# LPCB227_-_ACCELS.net
KiCad netlist of a schematic drawn in Altium Designer
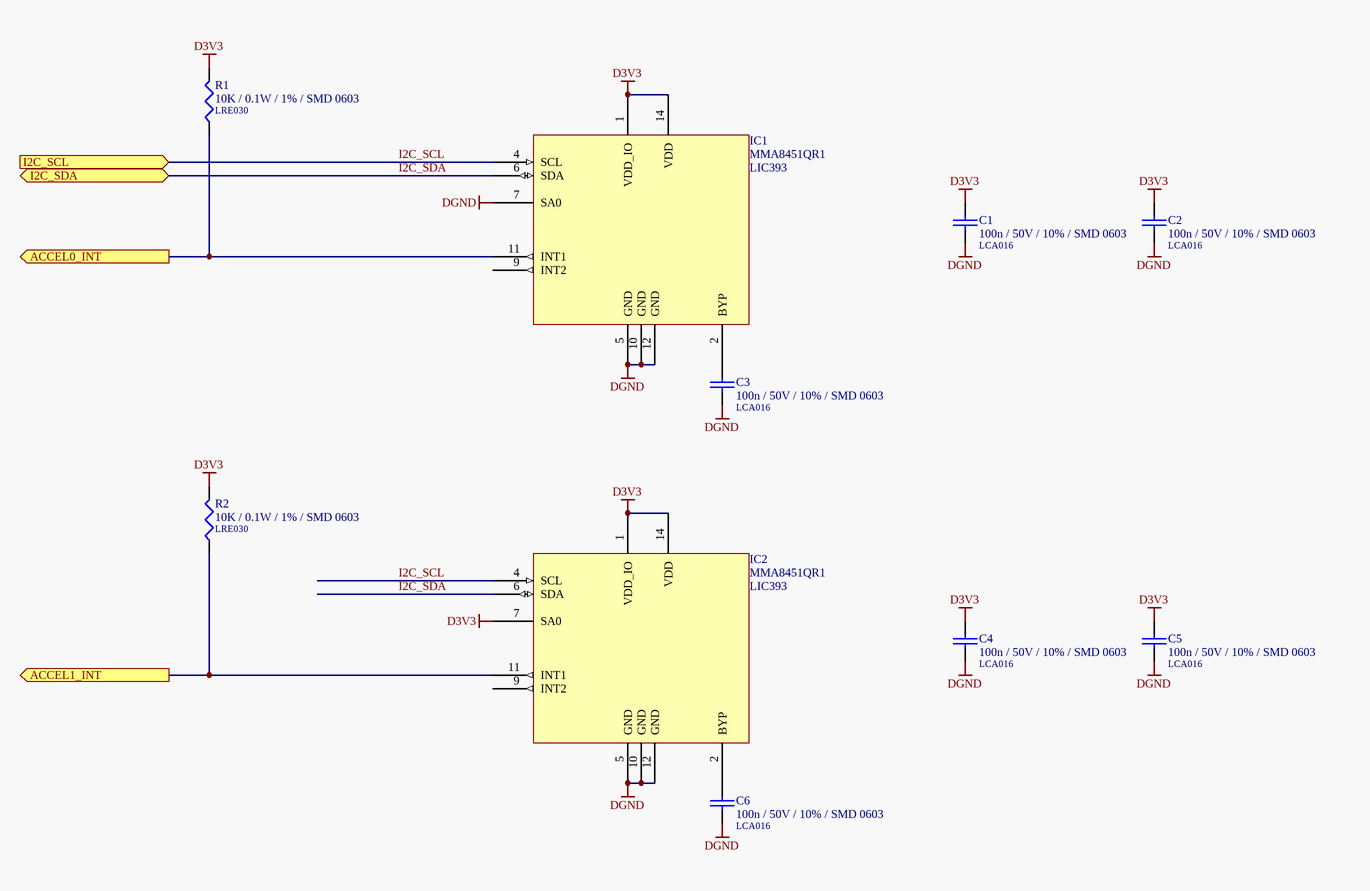
[diagram p0: LPCB227 - ACCELS.SchDoc]

(export (version "E")
  (design (tool "Eeschema 10.0.6"))
  (components
    (comp (ref "C1")
      (value "100n / 50V / 10% / SMD 0603")
      (footprint "LFP011__CC1608-0603-IPC7351_B")
      (description "Capacitor, Ceramic Chip, 100nF (0.1uF), 50V, 5%, SMD 0603 [LCA016]")
      (fields (field (name "LDL_NUMBER") "LCA016"))
      (libsource (lib "LDL_Capacitors") (part "100n / 50V / 10% / SMD 0603"))
    )
    (comp (ref "C2")
      (value "100n / 50V / 10% / SMD 0603")
      (footprint "LFP011__CC1608-0603-IPC7351_B")
      (description "Capacitor, Ceramic Chip, 100nF (0.1uF), 50V, 5%, SMD 0603 [LCA016]")
      (fields (field (name "LDL_NUMBER") "LCA016"))
      (libsource (lib "LDL_Capacitors") (part "100n / 50V / 10% / SMD 0603"))
    )
    (comp (ref "C3")
      (value "100n / 50V / 10% / SMD 0603")
      (footprint "LFP011__CC1608-0603-IPC7351_B")
      (description "Capacitor, Ceramic Chip, 100nF (0.1uF), 50V, 5%, SMD 0603 [LCA016]")
      (fields (field (name "LDL_NUMBER") "LCA016"))
      (libsource (lib "LDL_Capacitors") (part "100n / 50V / 10% / SMD 0603"))
    )
    (comp (ref "C4")
      (value "100n / 50V / 10% / SMD 0603")
      (footprint "LFP011__CC1608-0603-IPC7351_B")
      (description "Capacitor, Ceramic Chip, 100nF (0.1uF), 50V, 5%, SMD 0603 [LCA016]")
      (fields (field (name "LDL_NUMBER") "LCA016"))
      (libsource (lib "LDL_Capacitors") (part "100n / 50V / 10% / SMD 0603"))
    )
    (comp (ref "C5")
      (value "100n / 50V / 10% / SMD 0603")
      (footprint "LFP011__CC1608-0603-IPC7351_B")
      (description "Capacitor, Ceramic Chip, 100nF (0.1uF), 50V, 5%, SMD 0603 [LCA016]")
      (fields (field (name "LDL_NUMBER") "LCA016"))
      (libsource (lib "LDL_Capacitors") (part "100n / 50V / 10% / SMD 0603"))
    )
    (comp (ref "C6")
      (value "100n / 50V / 10% / SMD 0603")
      (footprint "LFP011__CC1608-0603-IPC7351_B")
      (description "Capacitor, Ceramic Chip, 100nF (0.1uF), 50V, 5%, SMD 0603 [LCA016]")
      (fields (field (name "LDL_NUMBER") "LCA016"))
      (libsource (lib "LDL_Capacitors") (part "100n / 50V / 10% / SMD 0603"))
    )
    (comp (ref "IC1")
      (value "MMA8451QR1")
      (footprint "LFP051__QFN16")
      (description "IC, Accelerometer, 3-Axis, 3.3V, I2C, SMD QFN16 [LIC393]")
      (fields (field (name "LDL_NUMBER") "LIC393"))
      (libsource (lib "LDL_Semiconductors") (part "MMA8451QR1"))
    )
    (comp (ref "IC2")
      (value "MMA8451QR1")
      (footprint "LFP051__QFN16")
      (description "IC, Accelerometer, 3-Axis, 3.3V, I2C, SMD QFN16 [LIC393]")
      (fields (field (name "LDL_NUMBER") "LIC393"))
      (libsource (lib "LDL_Semiconductors") (part "MMA8451QR1"))
    )
    (comp (ref "R1")
      (value "10K / 0.1W / 1% / SMD 0603")
      (footprint "LFP020__CR1608-0603-IPC7351_B")
      (description "Resistor, Ceramic Chip, 10K, 0.1W, 1%, SMD 0603 [LRE030]")
      (fields (field (name "LDL_NUMBER") "LRE030"))
      (libsource (lib "LDL_Resistors") (part "10K / 0.1W / 1% / SMD 0603"))
    )
    (comp (ref "R2")
      (value "10K / 0.1W / 1% / SMD 0603")
      (footprint "LFP020__CR1608-0603-IPC7351_B")
      (description "Resistor, Ceramic Chip, 10K, 0.1W, 1%, SMD 0603 [LRE030]")
      (fields (field (name "LDL_NUMBER") "LRE030"))
      (libsource (lib "LDL_Resistors") (part "10K / 0.1W / 1% / SMD 0603"))
    )
  )
  (nets
    (net (code "1") (name "/ACCEL0_INT") (class "Default")
      (node (ref "IC1") (pin "11") (pinfunction "INT1_11") (pintype "output"))
      (node (ref "R1") (pin "1") (pintype "passive"))
    )
    (net (code "2") (name "/ACCEL1_INT") (class "Default")
      (node (ref "IC2") (pin "11") (pinfunction "INT1_11") (pintype "output"))
      (node (ref "R2") (pin "1") (pintype "passive"))
    )
    (net (code "3") (name "/I2C_SCL") (class "Default")
      (node (ref "IC1") (pin "4") (pinfunction "SCL_4") (pintype "input"))
      (node (ref "IC2") (pin "4") (pinfunction "SCL_4") (pintype "input"))
    )
    (net (code "4") (name "/I2C_SDA") (class "Default")
      (node (ref "IC1") (pin "6") (pinfunction "SDA_6") (pintype "bidirectional"))
      (node (ref "IC2") (pin "6") (pinfunction "SDA_6") (pintype "bidirectional"))
    )
    (net (code "5") (name "D3V3") (class "Default")
      (node (ref "C1") (pin "1") (pintype "passive"))
      (node (ref "C2") (pin "1") (pintype "passive"))
      (node (ref "C4") (pin "1") (pintype "passive"))
      (node (ref "C5") (pin "1") (pintype "passive"))
      (node (ref "IC1") (pin "1") (pinfunction "VDD_IO_1") (pintype "power_in"))
      (node (ref "IC1") (pin "14") (pinfunction "VDD_14") (pintype "power_in"))
      (node (ref "IC2") (pin "1") (pinfunction "VDD_IO_1") (pintype "power_in"))
      (node (ref "IC2") (pin "14") (pinfunction "VDD_14") (pintype "power_in"))
      (node (ref "IC2") (pin "7") (pinfunction "SA0_7") (pintype "passive"))
      (node (ref "R1") (pin "2") (pintype "passive"))
      (node (ref "R2") (pin "2") (pintype "passive"))
    )
    (net (code "6") (name "DGND") (class "Default")
      (node (ref "C1") (pin "2") (pintype "passive"))
      (node (ref "C2") (pin "2") (pintype "passive"))
      (node (ref "C3") (pin "2") (pintype "passive"))
      (node (ref "C4") (pin "2") (pintype "passive"))
      (node (ref "C5") (pin "2") (pintype "passive"))
      (node (ref "C6") (pin "2") (pintype "passive"))
      (node (ref "IC1") (pin "10") (pinfunction "GND_10") (pintype "power_in"))
      (node (ref "IC1") (pin "12") (pinfunction "GND_12") (pintype "power_in"))
      (node (ref "IC1") (pin "5") (pinfunction "GND_5") (pintype "power_in"))
      (node (ref "IC1") (pin "7") (pinfunction "SA0_7") (pintype "passive"))
      (node (ref "IC2") (pin "10") (pinfunction "GND_10") (pintype "power_in"))
      (node (ref "IC2") (pin "12") (pinfunction "GND_12") (pintype "power_in"))
      (node (ref "IC2") (pin "5") (pinfunction "GND_5") (pintype "power_in"))
    )
    (net (code "7") (name "Net-(IC1-BYP)") (class "Default")
      (node (ref "C3") (pin "1") (pintype "passive"))
      (node (ref "IC1") (pin "2") (pinfunction "BYP_2") (pintype "passive"))
    )
    (net (code "8") (name "Net-(IC2-BYP)") (class "Default")
      (node (ref "C6") (pin "1") (pintype "passive"))
      (node (ref "IC2") (pin "2") (pinfunction "BYP_2") (pintype "passive"))
    )
    (net (code "9") (name "unconnected-(IC1-INT2-Pad9)") (class "Default")
      (node (ref "IC1") (pin "9") (pinfunction "INT2_9") (pintype "output"))
    )
    (net (code "10") (name "unconnected-(IC2-INT2-Pad9)") (class "Default")
      (node (ref "IC2") (pin "9") (pinfunction "INT2_9") (pintype "output"))
    )
  )
)
